# LCD_Joystick.net
KiCad netlist of a schematic drawn in Altium Designer
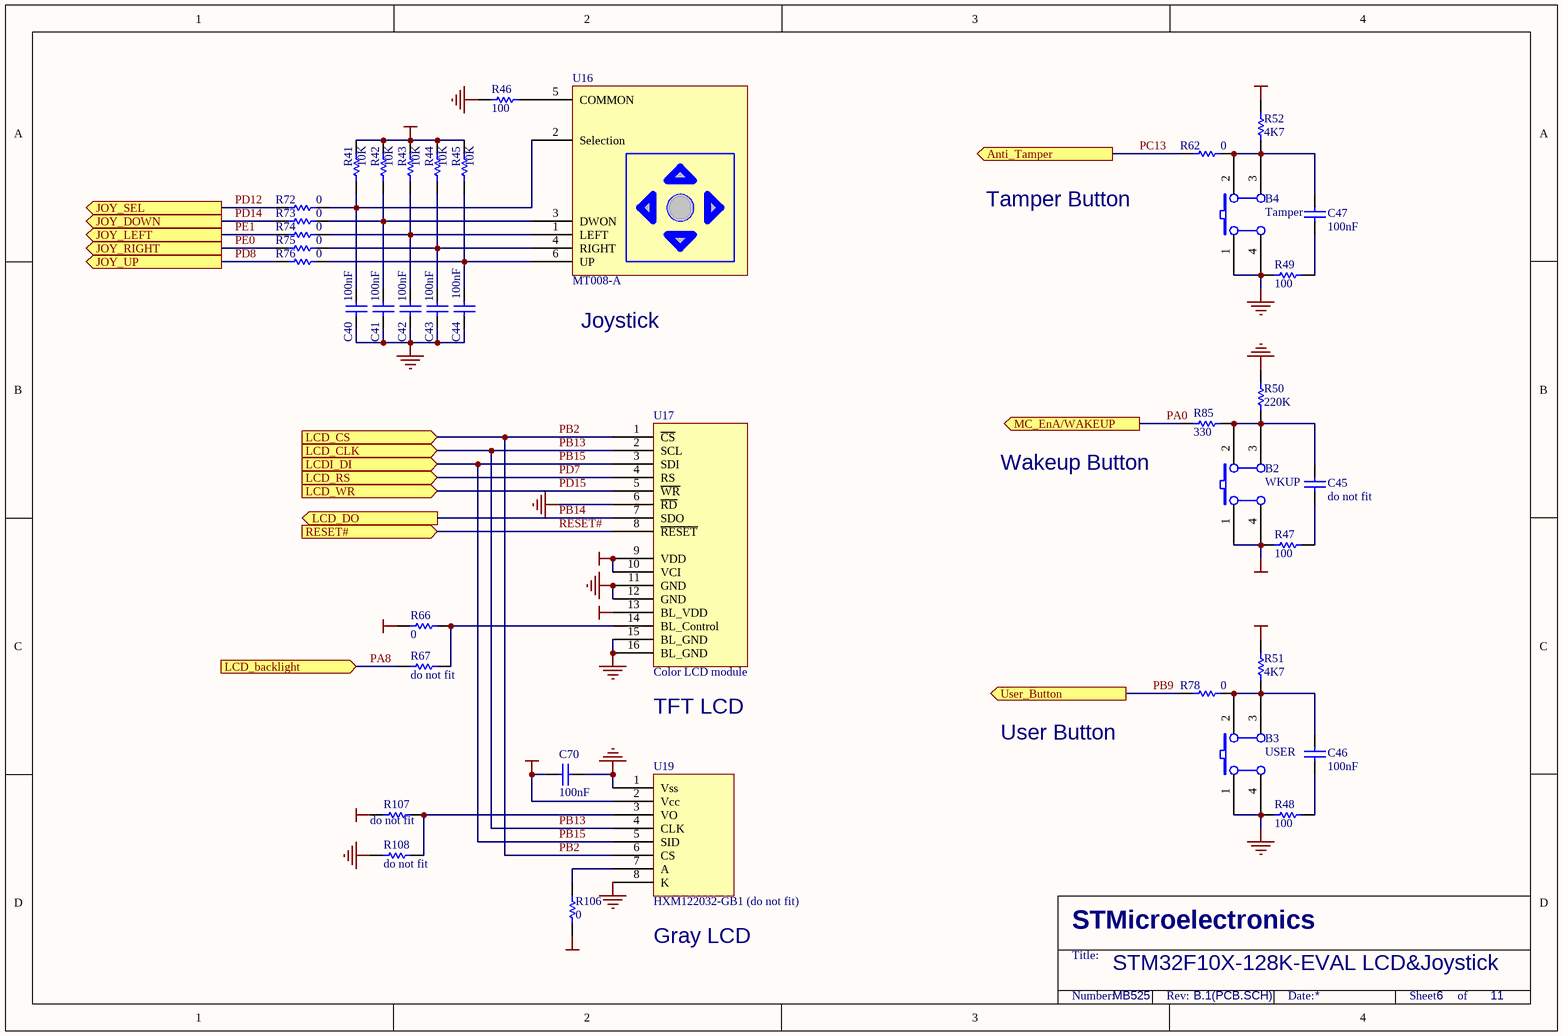
[diagram p0: LCD&Joystick.SchDoc]

(export (version "E")
  (design (tool "Eeschema 10.0.6"))
  (components
    (comp (ref "B2")
      (value "WKUP")
      (footprint "PB10")
      (description "SE PUSHBUTTON")
      (libsource (lib "Documents") (part "SW PUSHBUTTON"))
    )
    (comp (ref "B3")
      (value "USER")
      (footprint "PB10")
      (description "SE PUSHBUTTON")
      (libsource (lib "Documents") (part "SW PUSHBUTTON"))
    )
    (comp (ref "B4")
      (value "Tamper")
      (footprint "PB10")
      (description "SE PUSHBUTTON")
      (libsource (lib "Documents") (part "SW PUSHBUTTON"))
    )
    (comp (ref "C40")
      (value "100nF")
      (description "Capacitor")
      (fields (field (name "PUBLISHER") "Altium Limited"))
      (libsource (lib "Miscellaneous Devices") (part "CAP"))
    )
    (comp (ref "C41")
      (value "100nF")
      (description "Capacitor")
      (fields (field (name "PUBLISHER") "Altium Limited"))
      (libsource (lib "Miscellaneous Devices") (part "CAP"))
    )
    (comp (ref "C42")
      (value "100nF")
      (description "Capacitor")
      (fields (field (name "PUBLISHER") "Altium Limited"))
      (libsource (lib "Miscellaneous Devices") (part "CAP"))
    )
    (comp (ref "C43")
      (value "100nF")
      (description "Capacitor")
      (fields (field (name "PUBLISHER") "Altium Limited"))
      (libsource (lib "Miscellaneous Devices") (part "CAP"))
    )
    (comp (ref "C44")
      (value "100nF")
      (description "Capacitor")
      (fields (field (name "PUBLISHER") "Altium Limited"))
      (libsource (lib "Miscellaneous Devices") (part "CAP"))
    )
    (comp (ref "C45")
      (value "do not fit")
      (description "Capacitor")
      (fields (field (name "PUBLISHER") "Altium Limited"))
      (libsource (lib "Miscellaneous Devices") (part "CAP"))
    )
    (comp (ref "C46")
      (value "100nF")
      (description "Capacitor")
      (fields (field (name "PUBLISHER") "Altium Limited"))
      (libsource (lib "Miscellaneous Devices") (part "CAP"))
    )
    (comp (ref "C47")
      (value "100nF")
      (description "Capacitor")
      (fields (field (name "PUBLISHER") "Altium Limited"))
      (libsource (lib "Miscellaneous Devices") (part "CAP"))
    )
    (comp (ref "C70")
      (value "100nF")
      (description "Capacitor")
      (fields (field (name "PUBLISHER") "Altium Limited"))
      (libsource (lib "Miscellaneous Devices") (part "CAP"))
    )
    (comp (ref "R41")
      (value "10K")
      (description "Resistor")
      (fields (field (name "PUBLISHER") "Altium Limited"))
      (libsource (lib "Miscellaneous Devices") (part "Res1"))
    )
    (comp (ref "R42")
      (value "10K")
      (description "Resistor")
      (fields (field (name "PUBLISHER") "Altium Limited"))
      (libsource (lib "Miscellaneous Devices") (part "Res1"))
    )
    (comp (ref "R43")
      (value "10K")
      (description "Resistor")
      (fields (field (name "PUBLISHER") "Altium Limited"))
      (libsource (lib "Miscellaneous Devices") (part "Res1"))
    )
    (comp (ref "R44")
      (value "10K")
      (description "Resistor")
      (fields (field (name "PUBLISHER") "Altium Limited"))
      (libsource (lib "Miscellaneous Devices") (part "Res1"))
    )
    (comp (ref "R45")
      (value "10K")
      (description "Resistor")
      (fields (field (name "PUBLISHER") "Altium Limited"))
      (libsource (lib "Miscellaneous Devices") (part "Res1"))
    )
    (comp (ref "R46")
      (value "100")
      (description "Resistor")
      (fields (field (name "PUBLISHER") "Altium Limited"))
      (libsource (lib "Miscellaneous Devices") (part "Res1"))
    )
    (comp (ref "R47")
      (value "100")
      (description "Resistor")
      (fields (field (name "PUBLISHER") "Altium Limited"))
      (libsource (lib "Miscellaneous Devices") (part "Res1"))
    )
    (comp (ref "R48")
      (value "100")
      (description "Resistor")
      (fields (field (name "PUBLISHER") "Altium Limited"))
      (libsource (lib "Miscellaneous Devices") (part "Res1"))
    )
    (comp (ref "R49")
      (value "100")
      (description "Resistor")
      (fields (field (name "PUBLISHER") "Altium Limited"))
      (libsource (lib "Miscellaneous Devices") (part "Res1"))
    )
    (comp (ref "R50")
      (value "220K")
      (description "Resistor")
      (fields (field (name "PUBLISHER") "Altium Limited"))
      (libsource (lib "Miscellaneous Devices") (part "res1"))
    )
    (comp (ref "R51")
      (value "4K7")
      (description "Resistor")
      (fields (field (name "PUBLISHER") "Altium Limited"))
      (libsource (lib "Miscellaneous Devices") (part "res1"))
    )
    (comp (ref "R52")
      (value "4K7")
      (description "Resistor")
      (fields (field (name "PUBLISHER") "Altium Limited"))
      (libsource (lib "Miscellaneous Devices") (part "res1"))
    )
    (comp (ref "R62")
      (value "0")
      (description "Resistor")
      (fields (field (name "PUBLISHER") "Altium Limited"))
      (libsource (lib "Miscellaneous Devices") (part "Res1"))
    )
    (comp (ref "R66")
      (value "0")
      (description "Resistor")
      (fields (field (name "PUBLISHER") "Altium Limited"))
      (libsource (lib "Miscellaneous Devices") (part "Res1"))
    )
    (comp (ref "R67")
      (value "do not fit")
      (description "Resistor")
      (fields (field (name "PUBLISHER") "Altium Limited"))
      (libsource (lib "Miscellaneous Devices") (part "Res1"))
    )
    (comp (ref "R72")
      (value "0")
      (description "Resistor")
      (fields (field (name "PUBLISHER") "Altium Limited"))
      (libsource (lib "Miscellaneous Devices") (part "Res1"))
    )
    (comp (ref "R73")
      (value "0")
      (description "Resistor")
      (fields (field (name "PUBLISHER") "Altium Limited"))
      (libsource (lib "Miscellaneous Devices") (part "Res1"))
    )
    (comp (ref "R74")
      (value "0")
      (description "Resistor")
      (fields (field (name "PUBLISHER") "Altium Limited"))
      (libsource (lib "Miscellaneous Devices") (part "Res1"))
    )
    (comp (ref "R75")
      (value "0")
      (description "Resistor")
      (fields (field (name "PUBLISHER") "Altium Limited"))
      (libsource (lib "Miscellaneous Devices") (part "Res1"))
    )
    (comp (ref "R76")
      (value "0")
      (description "Resistor")
      (fields (field (name "PUBLISHER") "Altium Limited"))
      (libsource (lib "Miscellaneous Devices") (part "Res1"))
    )
    (comp (ref "R78")
      (value "0")
      (description "Resistor")
      (fields (field (name "PUBLISHER") "Altium Limited"))
      (libsource (lib "Miscellaneous Devices") (part "Res1"))
    )
    (comp (ref "R85")
      (value "330")
      (description "Resistor")
      (fields (field (name "PUBLISHER") "Altium Limited"))
      (libsource (lib "Miscellaneous Devices") (part "Res1"))
    )
    (comp (ref "R106")
      (value "0")
      (description "Resistor")
      (fields (field (name "PUBLISHER") "Altium Limited"))
      (libsource (lib "Miscellaneous Devices") (part "Res1"))
    )
    (comp (ref "R107")
      (value "do not fit")
      (description "Resistor")
      (fields (field (name "PUBLISHER") "Altium Limited"))
      (libsource (lib "Miscellaneous Devices") (part "Res1"))
    )
    (comp (ref "R108")
      (value "do not fit")
      (description "Resistor")
      (fields (field (name "PUBLISHER") "Altium Limited"))
      (libsource (lib "Miscellaneous Devices") (part "Res1"))
    )
    (comp (ref "U16") (value "MT008-A") (footprint "JOY") (libsource (lib "MB513") (part "MT-008A")))
    (comp (ref "U17")
      (value "Color LCD module")
      (footprint "AM240320A")
      (libsource (lib "MB525") (part "ColorLCD_module"))
    )
    (comp (ref "U19")
      (value "HXM122032-GB1 (do not fit)")
      (footprint "LCD12232-GB1")
      (libsource (lib "MB513") (part "HXM122032-GB1"))
    )
  )
  (nets
    (net (code "1") (name "+3V3") (class "Default")
      (node (ref "B2") (pin "1") (pinfunction "A0_1") (pintype "passive"))
      (node (ref "B2") (pin "4") (pinfunction "A1_4") (pintype "passive"))
      (node (ref "C70") (pin "1") (pinfunction "1_1") (pintype "passive"))
      (node (ref "R107") (pin "2") (pinfunction "2_2") (pintype "passive"))
      (node (ref "R41") (pin "1") (pinfunction "1_1") (pintype "passive"))
      (node (ref "R42") (pin "2") (pinfunction "2_2") (pintype "passive"))
      (node (ref "R43") (pin "2") (pinfunction "2_2") (pintype "passive"))
      (node (ref "R44") (pin "2") (pinfunction "2_2") (pintype "passive"))
      (node (ref "R45") (pin "2") (pinfunction "2_2") (pintype "passive"))
      (node (ref "R47") (pin "1") (pinfunction "1_1") (pintype "passive"))
      (node (ref "R51") (pin "2") (pinfunction "2_2") (pintype "passive"))
      (node (ref "R52") (pin "2") (pinfunction "2_2") (pintype "passive"))
      (node (ref "R66") (pin "2") (pinfunction "2_2") (pintype "passive"))
      (node (ref "U17") (pin "10") (pinfunction "VCI_10") (pintype "passive"))
      (node (ref "U17") (pin "13") (pinfunction "BL_VDD_13") (pintype "passive"))
      (node (ref "U17") (pin "9") (pinfunction "VDD_9") (pintype "passive"))
      (node (ref "U19") (pin "2") (pinfunction "Vcc_2") (pintype "passive"))
    )
    (net (code "2") (name "+5V") (class "Default")
      (node (ref "R106") (pin "1") (pinfunction "1_1") (pintype "passive"))
    )
    (net (code "3") (name "/PA0") (class "Default")
      (node (ref "R85") (pin "2") (pinfunction "2_2") (pintype "passive"))
    )
    (net (code "4") (name "/PA8") (class "Default")
      (node (ref "R67") (pin "1") (pinfunction "1_1") (pintype "passive"))
    )
    (net (code "5") (name "/PB2") (class "Default")
      (node (ref "U17") (pin "1") (pinfunction "~{CS}_1") (pintype "passive"))
      (node (ref "U19") (pin "6") (pinfunction "CS_6") (pintype "passive"))
    )
    (net (code "6") (name "/PB9") (class "Default")
      (node (ref "R78") (pin "2") (pinfunction "2_2") (pintype "passive"))
    )
    (net (code "7") (name "/PB13") (class "Default")
      (node (ref "U17") (pin "2") (pinfunction "SCL_2") (pintype "passive"))
      (node (ref "U19") (pin "4") (pinfunction "CLK_4") (pintype "passive"))
    )
    (net (code "8") (name "/PB14") (class "Default")
      (node (ref "U17") (pin "7") (pinfunction "SDO_7") (pintype "passive"))
    )
    (net (code "9") (name "/PB15") (class "Default")
      (node (ref "U17") (pin "3") (pinfunction "SDI_3") (pintype "passive"))
      (node (ref "U19") (pin "5") (pinfunction "SID_5") (pintype "passive"))
    )
    (net (code "10") (name "/PC13") (class "Default")
      (node (ref "R62") (pin "2") (pinfunction "2_2") (pintype "passive"))
    )
    (net (code "11") (name "/PD7") (class "Default")
      (node (ref "U17") (pin "4") (pinfunction "RS_4") (pintype "passive"))
    )
    (net (code "12") (name "/PD8") (class "Default")
      (node (ref "R76") (pin "2") (pinfunction "2_2") (pintype "passive"))
    )
    (net (code "13") (name "/PD12") (class "Default")
      (node (ref "R72") (pin "2") (pinfunction "2_2") (pintype "passive"))
    )
    (net (code "14") (name "/PD14") (class "Default")
      (node (ref "R73") (pin "2") (pinfunction "2_2") (pintype "passive"))
    )
    (net (code "15") (name "/PD15") (class "Default")
      (node (ref "U17") (pin "5") (pinfunction "~{WR}_5") (pintype "passive"))
    )
    (net (code "16") (name "/PE0") (class "Default")
      (node (ref "R75") (pin "2") (pinfunction "2_2") (pintype "passive"))
    )
    (net (code "17") (name "/PE1") (class "Default")
      (node (ref "R74") (pin "2") (pinfunction "2_2") (pintype "passive"))
    )
    (net (code "18") (name "/RESET#") (class "Default")
      (node (ref "U17") (pin "8") (pinfunction "~{RESET}_8") (pintype "passive"))
    )
    (net (code "19") (name "GND") (class "Default")
      (node (ref "B3") (pin "1") (pinfunction "A0_1") (pintype "passive"))
      (node (ref "B3") (pin "4") (pinfunction "A1_4") (pintype "passive"))
      (node (ref "B4") (pin "1") (pinfunction "A0_1") (pintype "passive"))
      (node (ref "B4") (pin "4") (pinfunction "A1_4") (pintype "passive"))
      (node (ref "C40") (pin "1") (pinfunction "1_1") (pintype "passive"))
      (node (ref "C41") (pin "1") (pinfunction "1_1") (pintype "passive"))
      (node (ref "C42") (pin "1") (pinfunction "1_1") (pintype "passive"))
      (node (ref "C43") (pin "1") (pinfunction "1_1") (pintype "passive"))
      (node (ref "C44") (pin "1") (pinfunction "1_1") (pintype "passive"))
      (node (ref "C70") (pin "2") (pinfunction "2_2") (pintype "passive"))
      (node (ref "R108") (pin "1") (pinfunction "1_1") (pintype "passive"))
      (node (ref "R46") (pin "1") (pinfunction "1_1") (pintype "passive"))
      (node (ref "R48") (pin "1") (pinfunction "1_1") (pintype "passive"))
      (node (ref "R49") (pin "1") (pinfunction "1_1") (pintype "passive"))
      (node (ref "R50") (pin "2") (pinfunction "2_2") (pintype "passive"))
      (node (ref "U17") (pin "11") (pinfunction "GND_11") (pintype "passive"))
      (node (ref "U17") (pin "12") (pinfunction "GND_12") (pintype "passive"))
      (node (ref "U17") (pin "15") (pinfunction "BL_GND_15") (pintype "passive"))
      (node (ref "U17") (pin "16") (pinfunction "BL_GND_16") (pintype "passive"))
      (node (ref "U17") (pin "6") (pinfunction "~{RD}_6") (pintype "passive"))
      (node (ref "U19") (pin "1") (pinfunction "Vss_1") (pintype "passive"))
      (node (ref "U19") (pin "8") (pinfunction "K_8") (pintype "passive"))
    )
    (net (code "20") (name "Net-(B2-B0)") (class "Default")
      (node (ref "B2") (pin "2") (pinfunction "B0_2") (pintype "passive"))
      (node (ref "B2") (pin "3") (pinfunction "B1_3") (pintype "passive"))
      (node (ref "C45") (pin "2") (pinfunction "2_2") (pintype "passive"))
      (node (ref "R50") (pin "1") (pinfunction "1_1") (pintype "passive"))
      (node (ref "R85") (pin "1") (pinfunction "1_1") (pintype "passive"))
    )
    (net (code "21") (name "Net-(B3-B0)") (class "Default")
      (node (ref "B3") (pin "2") (pinfunction "B0_2") (pintype "passive"))
      (node (ref "B3") (pin "3") (pinfunction "B1_3") (pintype "passive"))
      (node (ref "C46") (pin "2") (pinfunction "2_2") (pintype "passive"))
      (node (ref "R51") (pin "1") (pinfunction "1_1") (pintype "passive"))
      (node (ref "R78") (pin "1") (pinfunction "1_1") (pintype "passive"))
    )
    (net (code "22") (name "Net-(B4-B0)") (class "Default")
      (node (ref "B4") (pin "2") (pinfunction "B0_2") (pintype "passive"))
      (node (ref "B4") (pin "3") (pinfunction "B1_3") (pintype "passive"))
      (node (ref "C47") (pin "2") (pinfunction "2_2") (pintype "passive"))
      (node (ref "R52") (pin "1") (pinfunction "1_1") (pintype "passive"))
      (node (ref "R62") (pin "1") (pinfunction "1_1") (pintype "passive"))
    )
    (net (code "23") (name "Net-(C45-Pad1)") (class "Default")
      (node (ref "C45") (pin "1") (pinfunction "1_1") (pintype "passive"))
      (node (ref "R47") (pin "2") (pinfunction "2_2") (pintype "passive"))
    )
    (net (code "24") (name "Net-(C46-Pad1)") (class "Default")
      (node (ref "C46") (pin "1") (pinfunction "1_1") (pintype "passive"))
      (node (ref "R48") (pin "2") (pinfunction "2_2") (pintype "passive"))
    )
    (net (code "25") (name "Net-(C47-Pad1)") (class "Default")
      (node (ref "C47") (pin "1") (pinfunction "1_1") (pintype "passive"))
      (node (ref "R49") (pin "2") (pinfunction "2_2") (pintype "passive"))
    )
    (net (code "26") (name "Net-(U16-COMMON)") (class "Default")
      (node (ref "R46") (pin "2") (pinfunction "2_2") (pintype "passive"))
      (node (ref "U16") (pin "5") (pinfunction "COMMON_5") (pintype "passive"))
    )
    (net (code "27") (name "Net-(U16-DWON)") (class "Default")
      (node (ref "C41") (pin "2") (pinfunction "2_2") (pintype "passive"))
      (node (ref "R42") (pin "1") (pinfunction "1_1") (pintype "passive"))
      (node (ref "R73") (pin "1") (pinfunction "1_1") (pintype "passive"))
      (node (ref "U16") (pin "3") (pinfunction "DWON_3") (pintype "passive"))
    )
    (net (code "28") (name "Net-(U16-LEFT)") (class "Default")
      (node (ref "C42") (pin "2") (pinfunction "2_2") (pintype "passive"))
      (node (ref "R43") (pin "1") (pinfunction "1_1") (pintype "passive"))
      (node (ref "R74") (pin "1") (pinfunction "1_1") (pintype "passive"))
      (node (ref "U16") (pin "1") (pinfunction "LEFT_1") (pintype "passive"))
    )
    (net (code "29") (name "Net-(U16-RIGHT)") (class "Default")
      (node (ref "C43") (pin "2") (pinfunction "2_2") (pintype "passive"))
      (node (ref "R44") (pin "1") (pinfunction "1_1") (pintype "passive"))
      (node (ref "R75") (pin "1") (pinfunction "1_1") (pintype "passive"))
      (node (ref "U16") (pin "4") (pinfunction "RIGHT_4") (pintype "passive"))
    )
    (net (code "30") (name "Net-(U16-Selection)") (class "Default")
      (node (ref "C40") (pin "2") (pinfunction "2_2") (pintype "passive"))
      (node (ref "R41") (pin "2") (pinfunction "2_2") (pintype "passive"))
      (node (ref "R72") (pin "1") (pinfunction "1_1") (pintype "passive"))
      (node (ref "U16") (pin "2") (pinfunction "Selection_2") (pintype "passive"))
    )
    (net (code "31") (name "Net-(U16-UP)") (class "Default")
      (node (ref "C44") (pin "2") (pinfunction "2_2") (pintype "passive"))
      (node (ref "R45") (pin "1") (pinfunction "1_1") (pintype "passive"))
      (node (ref "R76") (pin "1") (pinfunction "1_1") (pintype "passive"))
      (node (ref "U16") (pin "6") (pinfunction "UP_6") (pintype "passive"))
    )
    (net (code "32") (name "Net-(U17-BL_Control)") (class "Default")
      (node (ref "R66") (pin "1") (pinfunction "1_1") (pintype "passive"))
      (node (ref "R67") (pin "2") (pinfunction "2_2") (pintype "passive"))
      (node (ref "U17") (pin "14") (pinfunction "BL_Control_14") (pintype "passive"))
    )
    (net (code "33") (name "Net-(U19-A)") (class "Default")
      (node (ref "R106") (pin "2") (pinfunction "2_2") (pintype "passive"))
      (node (ref "U19") (pin "7") (pinfunction "A_7") (pintype "passive"))
    )
    (net (code "34") (name "Net-(U19-VO)") (class "Default")
      (node (ref "R107") (pin "1") (pinfunction "1_1") (pintype "passive"))
      (node (ref "R108") (pin "2") (pinfunction "2_2") (pintype "passive"))
      (node (ref "U19") (pin "3") (pinfunction "VO_3") (pintype "passive"))
    )
  )
)
